# BK-GBC.net
KiCad netlist of a schematic drawn in EAGLE
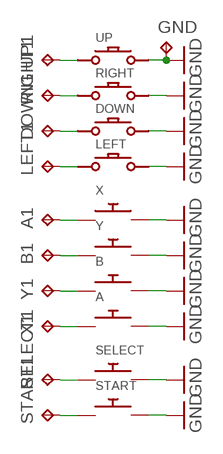
[diagram p0: schematic, sheet 1]

(export (version "E")
  (design (tool "Eeschema 10.0.6"))
  (components
    (comp (ref "A")
      (value "SWITCH_PUSH_VMUHOLE")
      (footprint "eagle-import:KEYPAD-VMU-HOLE")
      (libsource (lib "eagle-import") (part "SWITCH_PUSH_VMUHOLE"))
    )
    (comp (ref "A1")
      (value "TPPAD1-17")
      (footprint "eagle-import:P1-17")
      (libsource (lib "eagle-import") (part "TPPAD1-17"))
    )
    (comp (ref "B")
      (value "SWITCH_PUSH_VMUHOLE")
      (footprint "eagle-import:KEYPAD-VMU-HOLE")
      (libsource (lib "eagle-import") (part "SWITCH_PUSH_VMUHOLE"))
    )
    (comp (ref "B1")
      (value "TPPAD1-17")
      (footprint "eagle-import:P1-17")
      (libsource (lib "eagle-import") (part "TPPAD1-17"))
    )
    (comp (ref "DOWN")
      (value "DMG-BTNDPAD")
      (footprint "eagle-import:DS-LITE-DPAD")
      (libsource (lib "eagle-import") (part "DMG-BTNDPAD"))
    )
    (comp (ref "DOWN1")
      (value "TPPAD1-17")
      (footprint "eagle-import:P1-17")
      (libsource (lib "eagle-import") (part "TPPAD1-17"))
    )
    (comp (ref "GND")
      (value "TPPAD1-17")
      (footprint "eagle-import:P1-17")
      (libsource (lib "eagle-import") (part "TPPAD1-17"))
    )
    (comp (ref "LEFT")
      (value "DMG-BTNDPAD")
      (footprint "eagle-import:DS-LITE-DPAD")
      (libsource (lib "eagle-import") (part "DMG-BTNDPAD"))
    )
    (comp (ref "LEFT1")
      (value "TPPAD1-17")
      (footprint "eagle-import:P1-17")
      (libsource (lib "eagle-import") (part "TPPAD1-17"))
    )
    (comp (ref "RIGHT")
      (value "DMG-BTNDPAD")
      (footprint "eagle-import:DS-LITE-DPAD")
      (libsource (lib "eagle-import") (part "DMG-BTNDPAD"))
    )
    (comp (ref "RIGHT1")
      (value "TPPAD1-17")
      (footprint "eagle-import:P1-17")
      (libsource (lib "eagle-import") (part "TPPAD1-17"))
    )
    (comp (ref "SELECT")
      (value "SWITCH_PUSH_VMUSMALL-PAD")
      (footprint "eagle-import:SMALL_KEYPAD")
      (libsource (lib "eagle-import") (part "SWITCH_PUSH_VMUSMALL-PAD"))
    )
    (comp (ref "SELECT1")
      (value "TPPAD1-17")
      (footprint "eagle-import:P1-17")
      (libsource (lib "eagle-import") (part "TPPAD1-17"))
    )
    (comp (ref "START")
      (value "SWITCH_PUSH_VMUSMALL-PAD")
      (footprint "eagle-import:SMALL_KEYPAD")
      (libsource (lib "eagle-import") (part "SWITCH_PUSH_VMUSMALL-PAD"))
    )
    (comp (ref "START1")
      (value "TPPAD1-17")
      (footprint "eagle-import:P1-17")
      (libsource (lib "eagle-import") (part "TPPAD1-17"))
    )
    (comp (ref "UP")
      (value "DMG-BTNDPAD")
      (footprint "eagle-import:DS-LITE-DPAD")
      (libsource (lib "eagle-import") (part "DMG-BTNDPAD"))
    )
    (comp (ref "UP1")
      (value "TPPAD1-17")
      (footprint "eagle-import:P1-17")
      (libsource (lib "eagle-import") (part "TPPAD1-17"))
    )
    (comp (ref "X")
      (value "SWITCH_PUSH_VMULARGE-PAD")
      (footprint "eagle-import:KEYPAD_VMU_R26")
      (libsource (lib "eagle-import") (part "SWITCH_PUSH_VMULARGE-PAD"))
    )
    (comp (ref "X1")
      (value "TPPAD1-17")
      (footprint "eagle-import:P1-17")
      (libsource (lib "eagle-import") (part "TPPAD1-17"))
    )
    (comp (ref "Y")
      (value "SWITCH_PUSH_VMULARGE-PAD")
      (footprint "eagle-import:KEYPAD_VMU_R26")
      (libsource (lib "eagle-import") (part "SWITCH_PUSH_VMULARGE-PAD"))
    )
    (comp (ref "Y1")
      (value "TPPAD1-17")
      (footprint "eagle-import:P1-17")
      (libsource (lib "eagle-import") (part "TPPAD1-17"))
    )
  )
  (nets
    (net (code "1") (name "GND") (class "Default")
      (node (ref "A") (pin "2") (pinfunction "P$2_2") (pintype "passive"))
      (node (ref "B") (pin "2") (pinfunction "P$2_2") (pintype "passive"))
      (node (ref "DOWN") (pin "P$4") (pinfunction "P$2_P$4") (pintype "bidirectional"))
      (node (ref "GND") (pin "TP") (pinfunction "TP_TP") (pintype "input"))
      (node (ref "LEFT") (pin "P$4") (pinfunction "P$2_P$4") (pintype "bidirectional"))
      (node (ref "RIGHT") (pin "P$4") (pinfunction "P$2_P$4") (pintype "bidirectional"))
      (node (ref "SELECT") (pin "2") (pinfunction "P$2_2") (pintype "passive"))
      (node (ref "START") (pin "2") (pinfunction "P$2_2") (pintype "passive"))
      (node (ref "UP") (pin "P$4") (pinfunction "P$2_P$4") (pintype "bidirectional"))
      (node (ref "X") (pin "2") (pinfunction "P$2_2") (pintype "passive"))
      (node (ref "Y") (pin "2") (pinfunction "P$2_2") (pintype "passive"))
    )
    (net (code "2") (name "Net-(A-P$1)") (class "Default")
      (node (ref "A") (pin "1") (pinfunction "P$1_1") (pintype "passive"))
      (node (ref "X1") (pin "TP") (pinfunction "TP_TP") (pintype "input"))
    )
    (net (code "3") (name "Net-(B-P$1)") (class "Default")
      (node (ref "B") (pin "1") (pinfunction "P$1_1") (pintype "passive"))
      (node (ref "Y1") (pin "TP") (pinfunction "TP_TP") (pintype "input"))
    )
    (net (code "4") (name "Net-(DOWN-P$1)") (class "Default")
      (node (ref "DOWN") (pin "P$3") (pinfunction "P$1_P$3") (pintype "bidirectional"))
      (node (ref "DOWN1") (pin "TP") (pinfunction "TP_TP") (pintype "input"))
    )
    (net (code "5") (name "Net-(LEFT-P$1)") (class "Default")
      (node (ref "LEFT") (pin "P$3") (pinfunction "P$1_P$3") (pintype "bidirectional"))
      (node (ref "LEFT1") (pin "TP") (pinfunction "TP_TP") (pintype "input"))
    )
    (net (code "6") (name "Net-(RIGHT-P$1)") (class "Default")
      (node (ref "RIGHT") (pin "P$3") (pinfunction "P$1_P$3") (pintype "bidirectional"))
      (node (ref "RIGHT1") (pin "TP") (pinfunction "TP_TP") (pintype "input"))
    )
    (net (code "7") (name "Net-(SELECT-P$1)") (class "Default")
      (node (ref "SELECT") (pin "1") (pinfunction "P$1_1") (pintype "passive"))
      (node (ref "SELECT1") (pin "TP") (pinfunction "TP_TP") (pintype "input"))
    )
    (net (code "8") (name "Net-(START-P$1)") (class "Default")
      (node (ref "START") (pin "1") (pinfunction "P$1_1") (pintype "passive"))
      (node (ref "START1") (pin "TP") (pinfunction "TP_TP") (pintype "input"))
    )
    (net (code "9") (name "Net-(UP-P$1)") (class "Default")
      (node (ref "UP") (pin "P$3") (pinfunction "P$1_P$3") (pintype "bidirectional"))
      (node (ref "UP1") (pin "TP") (pinfunction "TP_TP") (pintype "input"))
    )
    (net (code "10") (name "Net-(X-P$1)") (class "Default")
      (node (ref "A1") (pin "TP") (pinfunction "TP_TP") (pintype "input"))
      (node (ref "X") (pin "1") (pinfunction "P$1_1") (pintype "passive"))
    )
    (net (code "11") (name "Net-(Y-P$1)") (class "Default")
      (node (ref "B1") (pin "TP") (pinfunction "TP_TP") (pintype "input"))
      (node (ref "Y") (pin "1") (pinfunction "P$1_1") (pintype "passive"))
    )
  )
)
